# Filters_n_Buffers.net
KiCad netlist of a schematic drawn in Altium Designer
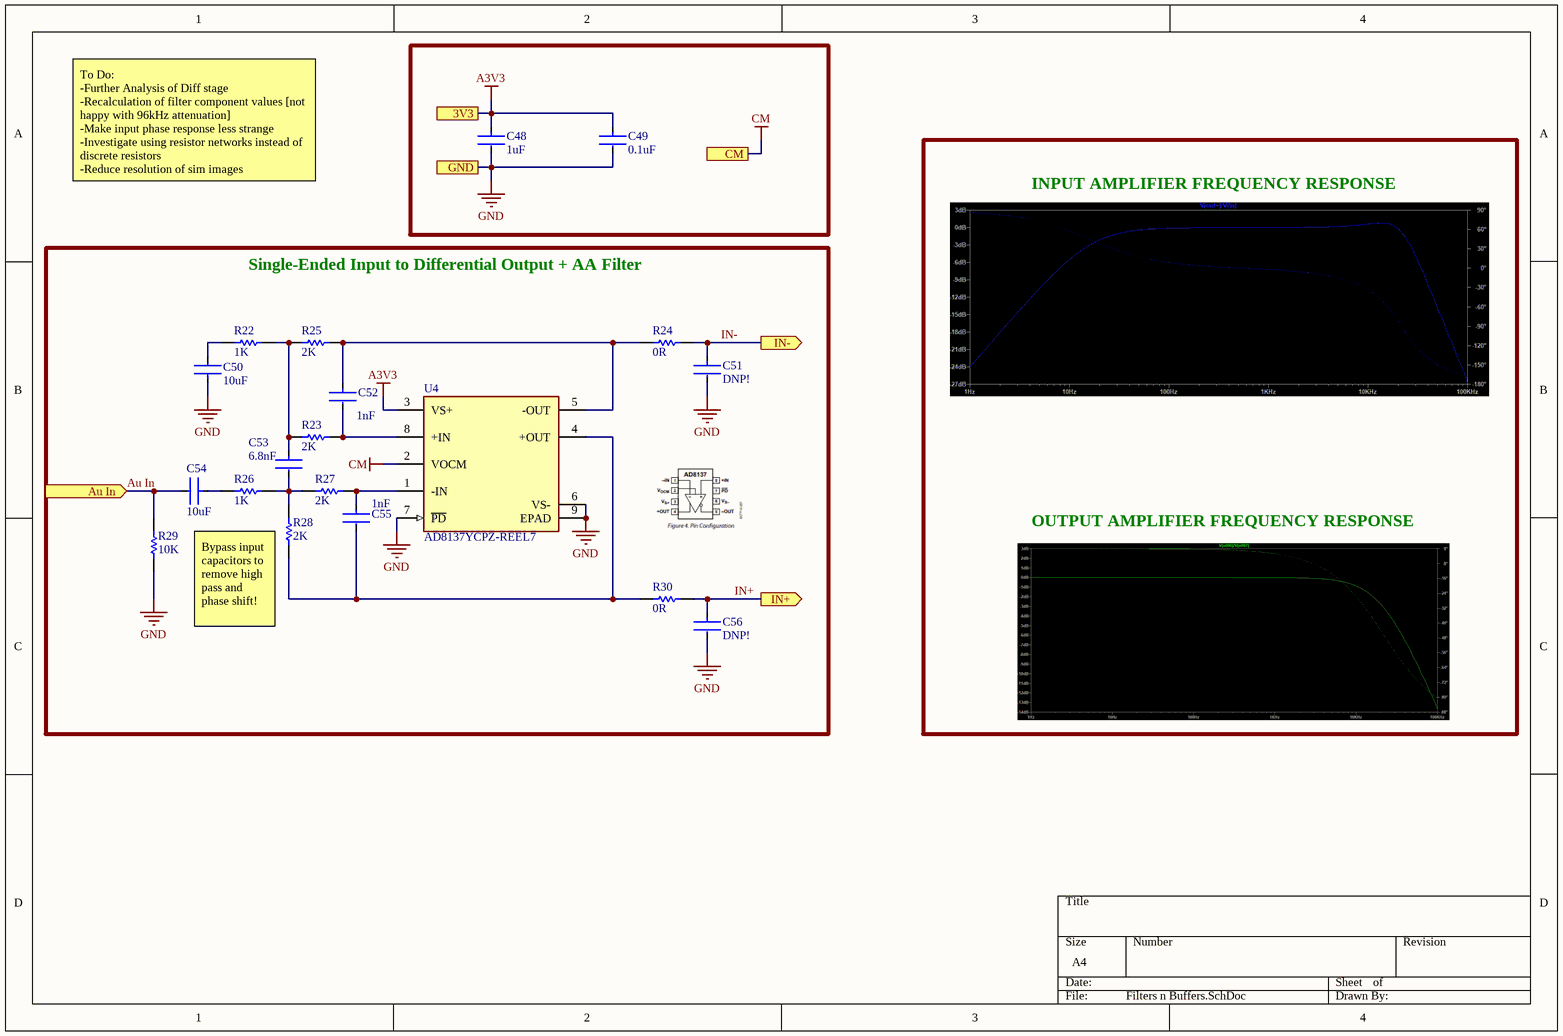
[diagram p0: Filters n Buffers.SchDoc]

(export (version "E")
  (design (tool "Eeschema 10.0.6"))
  (components
    (comp (ref "C48")
      (value "1uF")
      (footprint "FP-GRM15-MFG")
      (description "CAP CER 0.1UF 16V X7R 0402")
      (fields (field (name "MANUFACTURER PART NUMBER") "GRM155R71C104KA88D") (field (name "TOLERANCE") "10%"))
      (libsource (lib "Altium Content Vault") (part "236180d848d6139a670b325ea6854c9"))
    )
    (comp (ref "C49")
      (value "0.1uF")
      (footprint "FP-GRM15-MFG")
      (description "CAP CER 0.1UF 16V X7R 0402")
      (fields (field (name "MANUFACTURER PART NUMBER") "GRM155R71C104KA88D") (field (name "TOLERANCE") "10%"))
      (libsource (lib "Altium Content Vault") (part "236180d848d6139a670b325ea6854c9"))
    )
    (comp (ref "C50")
      (value "10uF")
      (footprint "FP-GRM15-MFG")
      (description "CAP CER 0.1UF 16V X7R 0402")
      (fields (field (name "MANUFACTURER PART NUMBER") "GRM155R71C104KA88D") (field (name "TOLERANCE") "10%"))
      (libsource (lib "Altium Content Vault") (part "236180d848d6139a670b325ea6854c9"))
    )
    (comp (ref "C51")
      (value "DNP!")
      (footprint "FP-GRM15-MFG")
      (description "CAP CER 0.1UF 16V X7R 0402")
      (fields (field (name "MANUFACTURER PART NUMBER") "GRM155R71C104KA88D") (field (name "TOLERANCE") "10%"))
      (libsource (lib "Altium Content Vault") (part "236180d848d6139a670b325ea6854c9"))
    )
    (comp (ref "C52")
      (value "1nF")
      (footprint "FP-GRM15-MFG")
      (description "CAP CER 0.1UF 16V X7R 0402")
      (fields (field (name "MANUFACTURER PART NUMBER") "GRM155R71C104KA88D") (field (name "TOLERANCE") "10%"))
      (libsource (lib "Altium Content Vault") (part "236180d848d6139a670b325ea6854c9"))
    )
    (comp (ref "C53")
      (value "6.8nF")
      (footprint "FP-GRM15-MFG")
      (description "CAP CER 0.1UF 16V X7R 0402")
      (fields (field (name "MANUFACTURER PART NUMBER") "GRM155R71C104KA88D") (field (name "TOLERANCE") "10%"))
      (libsource (lib "Altium Content Vault") (part "236180d848d6139a670b325ea6854c9"))
    )
    (comp (ref "C54")
      (value "10uF")
      (footprint "FP-GRM15-MFG")
      (description "CAP CER 0.1UF 16V X7R 0402")
      (fields (field (name "MANUFACTURER PART NUMBER") "GRM155R71C104KA88D") (field (name "TOLERANCE") "10%"))
      (libsource (lib "Altium Content Vault") (part "236180d848d6139a670b325ea6854c9"))
    )
    (comp (ref "C55")
      (value "1nF")
      (footprint "FP-GRM15-MFG")
      (description "CAP CER 0.1UF 16V X7R 0402")
      (fields (field (name "MANUFACTURER PART NUMBER") "GRM155R71C104KA88D") (field (name "TOLERANCE") "10%"))
      (libsource (lib "Altium Content Vault") (part "236180d848d6139a670b325ea6854c9"))
    )
    (comp (ref "C56")
      (value "DNP!")
      (footprint "FP-GRM15-MFG")
      (description "CAP CER 0.1UF 16V X7R 0402")
      (fields (field (name "MANUFACTURER PART NUMBER") "GRM155R71C104KA88D") (field (name "TOLERANCE") "10%"))
      (libsource (lib "Altium Content Vault") (part "236180d848d6139a670b325ea6854c9"))
    )
    (comp (ref "R22")
      (value "1K")
      (footprint "RESC1005X40X25LL05T05")
      (description "Chip Resistor, 0 Ohm, 0.1 W, -55 to 155 degC, 0402 (1005 Metric), RoHS, Tape and Reel")
      (fields (field (name "MANUFACTURER") "Panasonic") (field (name "TOLERANCE") "5%"))
      (libsource (lib "Altium Content Vault") (part "RES-2"))
    )
    (comp (ref "R23")
      (value "2K")
      (footprint "RESC1005X40X25LL05T05")
      (description "Chip Resistor, 0 Ohm, 0.1 W, -55 to 155 degC, 0402 (1005 Metric), RoHS, Tape and Reel")
      (fields (field (name "MANUFACTURER") "Panasonic") (field (name "TOLERANCE") "5%"))
      (libsource (lib "Altium Content Vault") (part "RES-2"))
    )
    (comp (ref "R24")
      (value "0R")
      (footprint "RESC1005X40X25LL05T05")
      (description "Chip Resistor, 0 Ohm, 0.1 W, -55 to 155 degC, 0402 (1005 Metric), RoHS, Tape and Reel")
      (fields (field (name "MANUFACTURER") "Panasonic") (field (name "TOLERANCE") "5%"))
      (libsource (lib "Altium Content Vault") (part "RES-2"))
    )
    (comp (ref "R25")
      (value "2K")
      (footprint "RESC1005X40X25LL05T05")
      (description "Chip Resistor, 0 Ohm, 0.1 W, -55 to 155 degC, 0402 (1005 Metric), RoHS, Tape and Reel")
      (fields (field (name "MANUFACTURER") "Panasonic") (field (name "TOLERANCE") "5%"))
      (libsource (lib "Altium Content Vault") (part "RES-2"))
    )
    (comp (ref "R26")
      (value "1K")
      (footprint "RESC1005X40X25LL05T05")
      (description "Chip Resistor, 0 Ohm, 0.1 W, -55 to 155 degC, 0402 (1005 Metric), RoHS, Tape and Reel")
      (fields (field (name "MANUFACTURER") "Panasonic") (field (name "TOLERANCE") "5%"))
      (libsource (lib "Altium Content Vault") (part "RES-2"))
    )
    (comp (ref "R27")
      (value "2K")
      (footprint "RESC1005X40X25LL05T05")
      (description "Chip Resistor, 0 Ohm, 0.1 W, -55 to 155 degC, 0402 (1005 Metric), RoHS, Tape and Reel")
      (fields (field (name "MANUFACTURER") "Panasonic") (field (name "TOLERANCE") "5%"))
      (libsource (lib "Altium Content Vault") (part "RES-2"))
    )
    (comp (ref "R28")
      (value "2K")
      (footprint "RESC1005X40X25LL05T05")
      (description "Chip Resistor, 0 Ohm, 0.1 W, -55 to 155 degC, 0402 (1005 Metric), RoHS, Tape and Reel")
      (fields (field (name "MANUFACTURER") "Panasonic") (field (name "TOLERANCE") "5%"))
      (libsource (lib "Altium Content Vault") (part "RES-2"))
    )
    (comp (ref "R29")
      (value "10K")
      (footprint "RESC1005X40X25LL05T05")
      (description "Chip Resistor, 0 Ohm, 0.1 W, -55 to 155 degC, 0402 (1005 Metric), RoHS, Tape and Reel")
      (fields (field (name "MANUFACTURER") "Panasonic") (field (name "TOLERANCE") "5%"))
      (libsource (lib "Altium Content Vault") (part "RES-2"))
    )
    (comp (ref "R30")
      (value "0R")
      (footprint "RESC1005X40X25LL05T05")
      (description "Chip Resistor, 0 Ohm, 0.1 W, -55 to 155 degC, 0402 (1005 Metric), RoHS, Tape and Reel")
      (fields (field (name "MANUFACTURER") "Panasonic") (field (name "TOLERANCE") "5%"))
      (libsource (lib "Altium Content Vault") (part "RES-2"))
    )
    (comp (ref "U4")
      (value "AD8137YCPZ-REEL7")
      (footprint "FP-CP-8-13-IPC_C")
      (description "IC OPAMP DIFF 1 CIRCUIT 8LFCSP")
      (libsource (lib "Altium Content Vault") (part "b3a67ab1d6d60b00f57058e55bbdee4"))
    )
  )
  (nets
    (net (code "1") (name "/Au In") (class "Default")
      (node (ref "C54") (pin "1") (pinfunction "1_1") (pintype "passive"))
      (node (ref "R29") (pin "1") (pinfunction "1_1") (pintype "passive"))
    )
    (net (code "2") (name "/IN+") (class "Default")
      (node (ref "C56") (pin "2") (pinfunction "2_2") (pintype "passive"))
      (node (ref "R30") (pin "2") (pinfunction "2_2") (pintype "passive"))
    )
    (net (code "3") (name "/IN-") (class "Default")
      (node (ref "C51") (pin "2") (pinfunction "2_2") (pintype "passive"))
      (node (ref "R24") (pin "2") (pinfunction "2_2") (pintype "passive"))
    )
    (net (code "4") (name "A3V3") (class "Default")
      (node (ref "C48") (pin "2") (pinfunction "2_2") (pintype "passive"))
      (node (ref "C49") (pin "2") (pinfunction "2_2") (pintype "passive"))
      (node (ref "U4") (pin "3") (pinfunction "VS+_3") (pintype "power_in"))
    )
    (net (code "5") (name "CM") (class "Default")
      (node (ref "U4") (pin "2") (pinfunction "VOCM_2") (pintype "passive"))
    )
    (net (code "6") (name "GND") (class "Default")
      (node (ref "C48") (pin "1") (pinfunction "1_1") (pintype "passive"))
      (node (ref "C49") (pin "1") (pinfunction "1_1") (pintype "passive"))
      (node (ref "C50") (pin "2") (pinfunction "2_2") (pintype "passive"))
      (node (ref "C51") (pin "1") (pinfunction "1_1") (pintype "passive"))
      (node (ref "C56") (pin "1") (pinfunction "1_1") (pintype "passive"))
      (node (ref "R29") (pin "2") (pinfunction "2_2") (pintype "passive"))
      (node (ref "U4") (pin "6") (pinfunction "VS-_6") (pintype "power_in"))
      (node (ref "U4") (pin "7") (pinfunction "~{PD}_7") (pintype "input"))
      (node (ref "U4") (pin "9") (pinfunction "EPAD_9") (pintype "power_in"))
    )
    (net (code "7") (name "Net-(C50-Pad1)") (class "Default")
      (node (ref "C50") (pin "1") (pinfunction "1_1") (pintype "passive"))
      (node (ref "R22") (pin "1") (pinfunction "1_1") (pintype "passive"))
    )
    (net (code "8") (name "Net-(C53-Pad1)") (class "Default")
      (node (ref "C53") (pin "1") (pinfunction "1_1") (pintype "passive"))
      (node (ref "R26") (pin "2") (pinfunction "2_2") (pintype "passive"))
      (node (ref "R27") (pin "1") (pinfunction "1_1") (pintype "passive"))
      (node (ref "R28") (pin "2") (pinfunction "2_2") (pintype "passive"))
    )
    (net (code "9") (name "Net-(C53-Pad2)") (class "Default")
      (node (ref "C53") (pin "2") (pinfunction "2_2") (pintype "passive"))
      (node (ref "R22") (pin "2") (pinfunction "2_2") (pintype "passive"))
      (node (ref "R23") (pin "1") (pinfunction "1_1") (pintype "passive"))
      (node (ref "R25") (pin "2") (pinfunction "2_2") (pintype "passive"))
    )
    (net (code "10") (name "Net-(C54-Pad2)") (class "Default")
      (node (ref "C54") (pin "2") (pinfunction "2_2") (pintype "passive"))
      (node (ref "R26") (pin "1") (pinfunction "1_1") (pintype "passive"))
    )
    (net (code "11") (name "Net-(U4-+IN)") (class "Default")
      (node (ref "C52") (pin "1") (pinfunction "1_1") (pintype "passive"))
      (node (ref "R23") (pin "2") (pinfunction "2_2") (pintype "passive"))
      (node (ref "U4") (pin "8") (pinfunction "+IN_8") (pintype "tri_state"))
    )
    (net (code "12") (name "Net-(U4-+OUT)") (class "Default")
      (node (ref "C55") (pin "1") (pinfunction "1_1") (pintype "passive"))
      (node (ref "R28") (pin "1") (pinfunction "1_1") (pintype "passive"))
      (node (ref "R30") (pin "1") (pinfunction "1_1") (pintype "passive"))
      (node (ref "U4") (pin "4") (pinfunction "+OUT_4") (pintype "passive"))
    )
    (net (code "13") (name "Net-(U4--IN)") (class "Default")
      (node (ref "C55") (pin "2") (pinfunction "2_2") (pintype "passive"))
      (node (ref "R27") (pin "2") (pinfunction "2_2") (pintype "passive"))
      (node (ref "U4") (pin "1") (pinfunction "-IN_1") (pintype "tri_state"))
    )
    (net (code "14") (name "Net-(U4--OUT)") (class "Default")
      (node (ref "C52") (pin "2") (pinfunction "2_2") (pintype "passive"))
      (node (ref "R24") (pin "1") (pinfunction "1_1") (pintype "passive"))
      (node (ref "R25") (pin "1") (pinfunction "1_1") (pintype "passive"))
      (node (ref "U4") (pin "5") (pinfunction "-OUT_5") (pintype "passive"))
    )
  )
)
